# ActiveRoute_SCH.net
KiCad netlist of a schematic drawn in Altium Designer
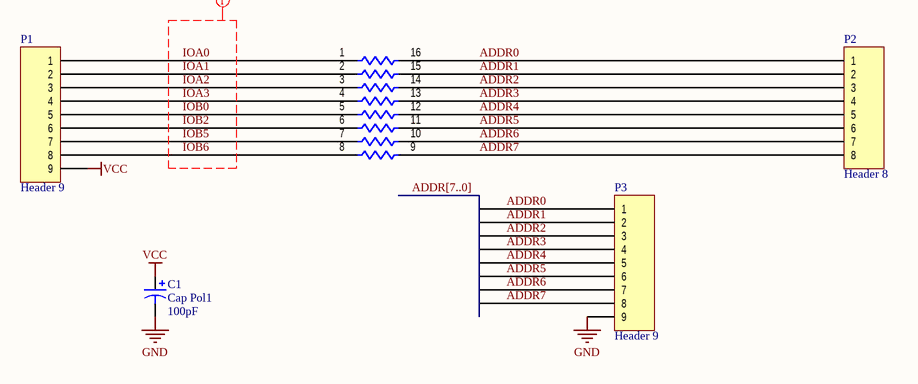
[diagram p0: ActiveRoute SCH.SchDoc]

(export (version "E")
  (design (tool "Eeschema 10.0.6"))
  (components
    (comp (ref "C1")
      (value "Cap Pol1")
      (footprint "RB7.6-15")
      (description "Polarized Capacitor (Radial)")
      (fields (field (name "ALTIUM_VALUE") "100pF") (field (name "PUBLISHER") "Altium Limited"))
      (libsource (lib "Miscellaneous Devices") (part "Cap Pol1"))
    )
    (comp (ref "P1")
      (value "Header 9")
      (footprint "HDR1X9")
      (description "Header, 9-Pin")
      (fields (field (name "PUBLISHER") "Altium Limited"))
      (libsource (lib "Miscellaneous Connectors") (part "Header 9"))
    )
    (comp (ref "P2")
      (value "Header 8")
      (footprint "HDR1X8")
      (description "Header, 8-Pin")
      (fields (field (name "PUBLISHER") "Altium Limited"))
      (libsource (lib "Miscellaneous Connectors") (part "Header 8"))
    )
    (comp (ref "P3")
      (value "Header 9")
      (footprint "HDR1X9")
      (description "Header, 9-Pin")
      (fields (field (name "PUBLISHER") "Altium Limited"))
      (libsource (lib "") (part "Header 9_1"))
    )
    (comp (ref "R1")
      (value "Res Pack1")
      (footprint "SOIC16_N")
      (description "Isolated Resistor Network - Parts")
      (fields (field (name "PUBLISHER") "Altium Limited"))
      (libsource (lib "Miscellaneous Devices") (part "Res Pack1"))
    )
  )
  (nets
    (net (code "1") (name "/ADDR0") (class "Default")
      (node (ref "P2") (pin "1") (pinfunction "1_1") (pintype "passive"))
      (node (ref "P3") (pin "1") (pinfunction "1_1") (pintype "passive"))
      (node (ref "R1") (pin "16") (pinfunction "16_16") (pintype "passive"))
    )
    (net (code "2") (name "/ADDR1") (class "Default")
      (node (ref "P2") (pin "2") (pinfunction "2_2") (pintype "passive"))
      (node (ref "P3") (pin "2") (pinfunction "2_2") (pintype "passive"))
      (node (ref "R1") (pin "15") (pinfunction "15_15") (pintype "passive"))
    )
    (net (code "3") (name "/ADDR2") (class "Default")
      (node (ref "P2") (pin "3") (pinfunction "3_3") (pintype "passive"))
      (node (ref "P3") (pin "3") (pinfunction "3_3") (pintype "passive"))
      (node (ref "R1") (pin "14") (pinfunction "14_14") (pintype "passive"))
    )
    (net (code "4") (name "/ADDR3") (class "Default")
      (node (ref "P2") (pin "4") (pinfunction "4_4") (pintype "passive"))
      (node (ref "P3") (pin "4") (pinfunction "4_4") (pintype "passive"))
      (node (ref "R1") (pin "13") (pinfunction "13_13") (pintype "passive"))
    )
    (net (code "5") (name "/ADDR4") (class "Default")
      (node (ref "P2") (pin "5") (pinfunction "5_5") (pintype "passive"))
      (node (ref "P3") (pin "5") (pinfunction "5_5") (pintype "passive"))
      (node (ref "R1") (pin "12") (pinfunction "12_12") (pintype "passive"))
    )
    (net (code "6") (name "/ADDR5") (class "Default")
      (node (ref "P2") (pin "6") (pinfunction "6_6") (pintype "passive"))
      (node (ref "P3") (pin "6") (pinfunction "6_6") (pintype "passive"))
      (node (ref "R1") (pin "11") (pinfunction "11_11") (pintype "passive"))
    )
    (net (code "7") (name "/ADDR6") (class "Default")
      (node (ref "P2") (pin "7") (pinfunction "7_7") (pintype "passive"))
      (node (ref "P3") (pin "7") (pinfunction "7_7") (pintype "passive"))
      (node (ref "R1") (pin "10") (pinfunction "10_10") (pintype "passive"))
    )
    (net (code "8") (name "/ADDR7") (class "Default")
      (node (ref "P2") (pin "8") (pinfunction "8_8") (pintype "passive"))
      (node (ref "P3") (pin "8") (pinfunction "8_8") (pintype "passive"))
      (node (ref "R1") (pin "9") (pinfunction "9_9") (pintype "passive"))
    )
    (net (code "10") (name "/IOA0") (class "Default")
      (node (ref "P1") (pin "1") (pinfunction "1_1") (pintype "passive"))
      (node (ref "R1") (pin "1") (pinfunction "1_1") (pintype "passive"))
    )
    (net (code "11") (name "/IOA1") (class "Default")
      (node (ref "P1") (pin "2") (pinfunction "2_2") (pintype "passive"))
      (node (ref "R1") (pin "2") (pinfunction "2_2") (pintype "passive"))
    )
    (net (code "12") (name "/IOA2") (class "Default")
      (node (ref "P1") (pin "3") (pinfunction "3_3") (pintype "passive"))
      (node (ref "R1") (pin "3") (pinfunction "3_3") (pintype "passive"))
    )
    (net (code "13") (name "/IOA3") (class "Default")
      (node (ref "P1") (pin "4") (pinfunction "4_4") (pintype "passive"))
      (node (ref "R1") (pin "4") (pinfunction "4_4") (pintype "passive"))
    )
    (net (code "14") (name "/IOB0") (class "Default")
      (node (ref "P1") (pin "5") (pinfunction "5_5") (pintype "passive"))
      (node (ref "R1") (pin "5") (pinfunction "5_5") (pintype "passive"))
    )
    (net (code "15") (name "/IOB2") (class "Default")
      (node (ref "P1") (pin "6") (pinfunction "6_6") (pintype "passive"))
      (node (ref "R1") (pin "6") (pinfunction "6_6") (pintype "passive"))
    )
    (net (code "16") (name "/IOB5") (class "Default")
      (node (ref "P1") (pin "7") (pinfunction "7_7") (pintype "passive"))
      (node (ref "R1") (pin "7") (pinfunction "7_7") (pintype "passive"))
    )
    (net (code "17") (name "/IOB6") (class "Default")
      (node (ref "P1") (pin "8") (pinfunction "8_8") (pintype "passive"))
      (node (ref "R1") (pin "8") (pinfunction "8_8") (pintype "passive"))
    )
    (net (code "18") (name "GND") (class "Default")
      (node (ref "C1") (pin "2") (pinfunction "2_2") (pintype "passive"))
      (node (ref "P3") (pin "9") (pinfunction "9_9") (pintype "passive"))
    )
    (net (code "19") (name "VCC") (class "Default")
      (node (ref "C1") (pin "1") (pinfunction "1_1") (pintype "passive"))
      (node (ref "P1") (pin "9") (pinfunction "9_9") (pintype "passive"))
    )
  )
)
